# 2_FTDI.net
KiCad netlist of a schematic drawn in Altium Designer
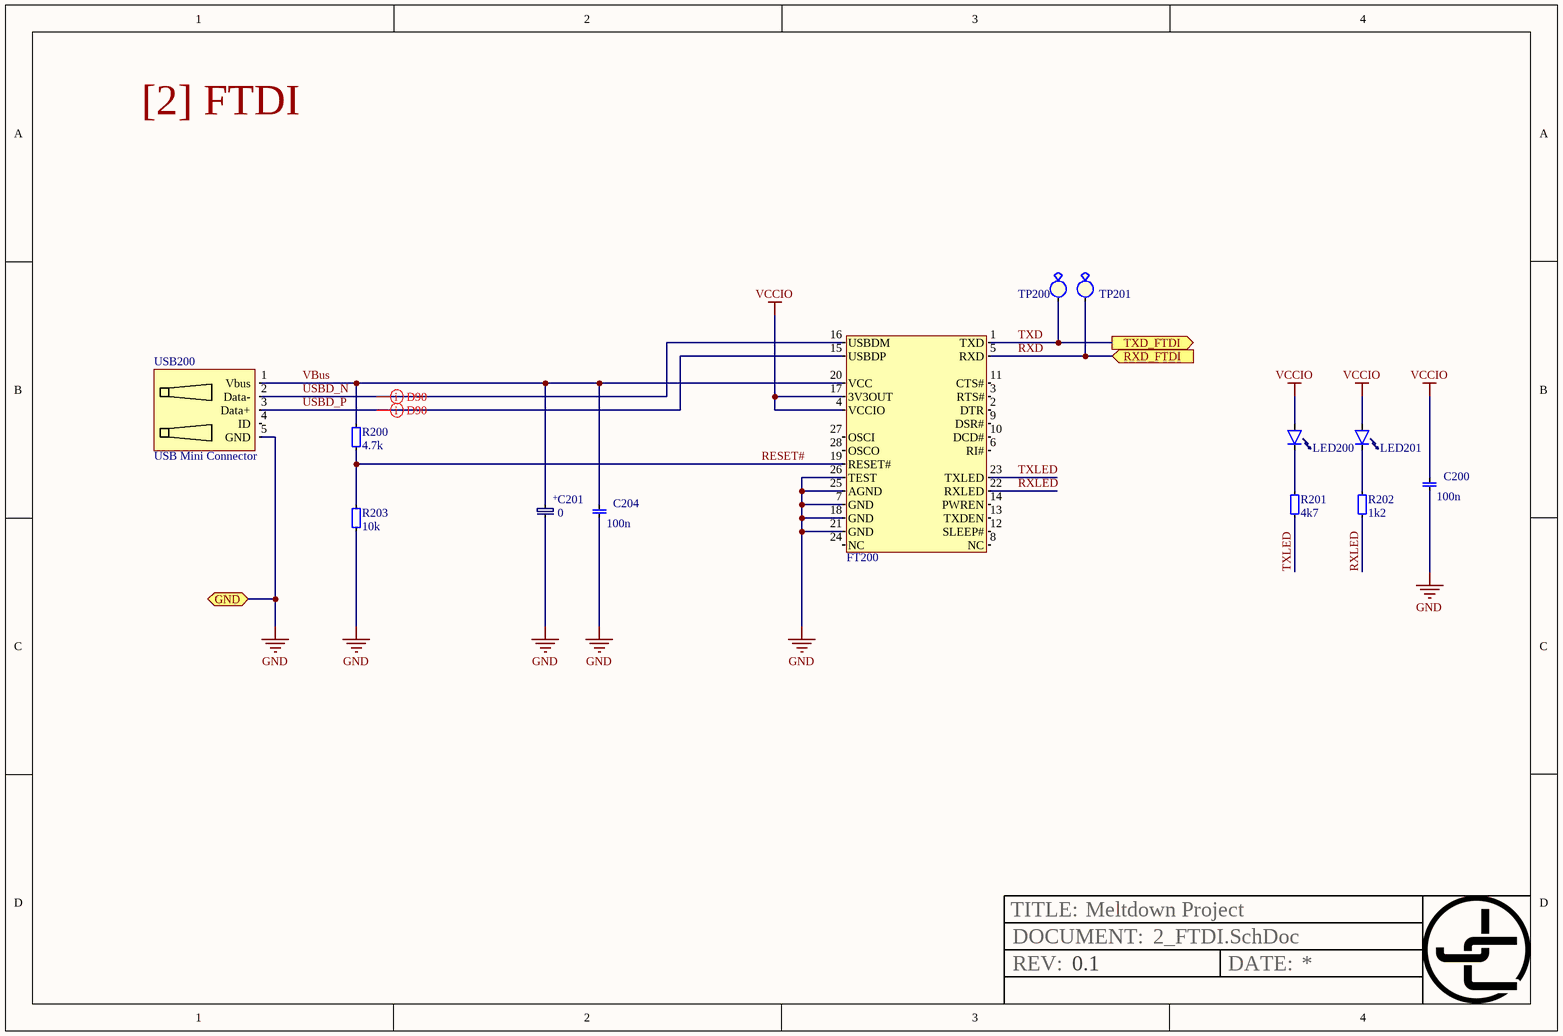
[diagram p0: 2_FTDI.SchDoc]

(export (version "E")
  (design (tool "Eeschema 10.0.6"))
  (components
    (comp (ref "C200")
      (value "100n")
      (footprint "0603 cap")
      (fields (field (name "Comment") "0603, capacitor"))
      (libsource (lib "jclib") (part "0603, capacitor"))
    )
    (comp (ref "C201")
      (value "0")
      (footprint "CASE_B")
      (fields (field (name "Comment") "Cap, case B"))
      (libsource (lib "jclib") (part "Cap, case B"))
    )
    (comp (ref "C204")
      (value "100n")
      (footprint "0603 cap")
      (fields (field (name "Comment") "0603, capacitor"))
      (libsource (lib "jclib") (part "0603, capacitor"))
    )
    (comp (ref "FT200")
      (value "FT232R")
      (footprint "SOP28")
      (description "USB UART IC")
      (libsource (lib "jclib") (part "FT232R"))
    )
    (comp (ref "LED200")
      (value "0805, LED")
      (footprint "0805_led")
      (libsource (lib "jclib") (part "0805, LED"))
    )
    (comp (ref "LED201")
      (value "0805, LED")
      (footprint "0805_led")
      (libsource (lib "jclib") (part "0805, LED"))
    )
    (comp (ref "R200")
      (value "4.7k")
      (footprint "0603")
      (fields (field (name "Comment") "0603, resistor"))
      (libsource (lib "jclib") (part "0603, resistor"))
    )
    (comp (ref "R201")
      (value "4k7")
      (footprint "0603")
      (fields (field (name "Comment") "0603, resistor"))
      (libsource (lib "jclib") (part "0603, resistor"))
    )
    (comp (ref "R202")
      (value "1k2")
      (footprint "0603")
      (fields (field (name "Comment") "0603, resistor"))
      (libsource (lib "jclib") (part "0603, resistor"))
    )
    (comp (ref "R203")
      (value "10k")
      (footprint "0603")
      (fields (field (name "Comment") "0603, resistor"))
      (libsource (lib "jclib") (part "0603, resistor"))
    )
    (comp (ref "TP200")
      (value "Test Point")
      (footprint "testPoint")
      (libsource (lib "jclib") (part "Test Point"))
    )
    (comp (ref "TP201")
      (value "Test Point")
      (footprint "testPoint")
      (libsource (lib "jclib") (part "Test Point"))
    )
    (comp (ref "USB200")
      (value "USB Mini Connector")
      (footprint "USB Mini TH")
      (libsource (lib "jclib") (part "USB Mini Connector"))
    )
  )
  (nets
    (net (code "1") (name "/RESET#") (class "Default")
      (node (ref "FT200") (pin "19") (pinfunction "RESET#_19") (pintype "passive"))
      (node (ref "R200") (pin "1") (pinfunction "1_1") (pintype "passive"))
      (node (ref "R203") (pin "0") (pinfunction "0_0") (pintype "passive"))
    )
    (net (code "2") (name "/RXD") (class "Default")
      (node (ref "FT200") (pin "5") (pinfunction "RXD_5") (pintype "passive"))
      (node (ref "TP201") (pin "0") (pinfunction "0_0") (pintype "passive"))
    )
    (net (code "3") (name "/RXLED") (class "Default")
      (node (ref "FT200") (pin "22") (pinfunction "RXLED_22") (pintype "passive"))
      (node (ref "R202") (pin "1") (pinfunction "1_1") (pintype "passive"))
    )
    (net (code "4") (name "/TXD") (class "Default")
      (node (ref "FT200") (pin "1") (pinfunction "TXD_1") (pintype "passive"))
      (node (ref "TP200") (pin "0") (pinfunction "0_0") (pintype "passive"))
    )
    (net (code "5") (name "/TXLED") (class "Default")
      (node (ref "FT200") (pin "23") (pinfunction "TXLED_23") (pintype "passive"))
      (node (ref "R201") (pin "1") (pinfunction "1_1") (pintype "passive"))
    )
    (net (code "6") (name "/USBD_N") (class "Default")
      (node (ref "FT200") (pin "16") (pinfunction "USBDM_16") (pintype "passive"))
      (node (ref "USB200") (pin "2") (pinfunction "Data-_2") (pintype "passive"))
    )
    (net (code "7") (name "/USBD_P") (class "Default")
      (node (ref "FT200") (pin "15") (pinfunction "USBDP_15") (pintype "passive"))
      (node (ref "USB200") (pin "3") (pinfunction "Data+_3") (pintype "passive"))
    )
    (net (code "8") (name "/VBus") (class "Default")
      (node (ref "C201") (pin "2") (pinfunction "2_2") (pintype "passive"))
      (node (ref "C204") (pin "1") (pinfunction "1_1") (pintype "passive"))
      (node (ref "FT200") (pin "20") (pinfunction "VCC_20") (pintype "passive"))
      (node (ref "R200") (pin "0") (pinfunction "0_0") (pintype "passive"))
      (node (ref "USB200") (pin "1") (pinfunction "Vbus_1") (pintype "passive"))
    )
    (net (code "9") (name "GND") (class "Default")
      (node (ref "C200") (pin "0") (pinfunction "0_0") (pintype "passive"))
      (node (ref "C201") (pin "1") (pinfunction "1_1") (pintype "passive"))
      (node (ref "C204") (pin "0") (pinfunction "0_0") (pintype "passive"))
      (node (ref "FT200") (pin "18") (pinfunction "GND_18") (pintype "passive"))
      (node (ref "FT200") (pin "21") (pinfunction "GND_21") (pintype "passive"))
      (node (ref "FT200") (pin "25") (pinfunction "AGND_25") (pintype "passive"))
      (node (ref "FT200") (pin "26") (pinfunction "TEST_26") (pintype "passive"))
      (node (ref "FT200") (pin "7") (pinfunction "GND_7") (pintype "passive"))
      (node (ref "R203") (pin "1") (pinfunction "1_1") (pintype "passive"))
      (node (ref "USB200") (pin "5") (pinfunction "GND_5") (pintype "passive"))
    )
    (net (code "10") (name "Net-(LED200-Cathode)") (class "Default")
      (node (ref "LED200") (pin "0") (pinfunction "Cathode_0") (pintype "passive"))
      (node (ref "R201") (pin "0") (pinfunction "0_0") (pintype "passive"))
    )
    (net (code "11") (name "Net-(LED201-Cathode)") (class "Default")
      (node (ref "LED201") (pin "0") (pinfunction "Cathode_0") (pintype "passive"))
      (node (ref "R202") (pin "0") (pinfunction "0_0") (pintype "passive"))
    )
    (net (code "12") (name "VCCIO") (class "Default")
      (node (ref "C200") (pin "1") (pinfunction "1_1") (pintype "passive"))
      (node (ref "FT200") (pin "17") (pinfunction "3V3OUT_17") (pintype "passive"))
      (node (ref "FT200") (pin "4") (pinfunction "VCCIO_4") (pintype "passive"))
      (node (ref "LED200") (pin "1") (pinfunction "1_1") (pintype "passive"))
      (node (ref "LED201") (pin "1") (pinfunction "1_1") (pintype "passive"))
    )
    (net (code "13") (name "unconnected-(FT200-CTS#-Pad11)") (class "Default")
      (node (ref "FT200") (pin "11") (pinfunction "CTS#_11") (pintype "passive"))
    )
    (net (code "14") (name "unconnected-(FT200-DCD#-Pad10)") (class "Default")
      (node (ref "FT200") (pin "10") (pinfunction "DCD#_10") (pintype "passive"))
    )
    (net (code "15") (name "unconnected-(FT200-DSR#-Pad9)") (class "Default")
      (node (ref "FT200") (pin "9") (pinfunction "DSR#_9") (pintype "passive"))
    )
    (net (code "16") (name "unconnected-(FT200-DTR-Pad2)") (class "Default")
      (node (ref "FT200") (pin "2") (pinfunction "DTR_2") (pintype "passive"))
    )
    (net (code "17") (name "unconnected-(FT200-NC-Pad8)") (class "Default")
      (node (ref "FT200") (pin "8") (pinfunction "NC_8") (pintype "passive"))
    )
    (net (code "18") (name "unconnected-(FT200-NC-Pad24)") (class "Default")
      (node (ref "FT200") (pin "24") (pinfunction "NC_24") (pintype "passive"))
    )
    (net (code "19") (name "unconnected-(FT200-OSCI-Pad27)") (class "Default")
      (node (ref "FT200") (pin "27") (pinfunction "OSCI_27") (pintype "passive"))
    )
    (net (code "20") (name "unconnected-(FT200-OSCO-Pad28)") (class "Default")
      (node (ref "FT200") (pin "28") (pinfunction "OSCO_28") (pintype "passive"))
    )
    (net (code "21") (name "unconnected-(FT200-PWREN-Pad14)") (class "Default")
      (node (ref "FT200") (pin "14") (pinfunction "PWREN_14") (pintype "passive"))
    )
    (net (code "22") (name "unconnected-(FT200-RI#-Pad6)") (class "Default")
      (node (ref "FT200") (pin "6") (pinfunction "RI#_6") (pintype "passive"))
    )
    (net (code "23") (name "unconnected-(FT200-RTS#-Pad3)") (class "Default")
      (node (ref "FT200") (pin "3") (pinfunction "RTS#_3") (pintype "passive"))
    )
    (net (code "24") (name "unconnected-(FT200-SLEEP#-Pad12)") (class "Default")
      (node (ref "FT200") (pin "12") (pinfunction "SLEEP#_12") (pintype "passive"))
    )
    (net (code "25") (name "unconnected-(FT200-TXDEN-Pad13)") (class "Default")
      (node (ref "FT200") (pin "13") (pinfunction "TXDEN_13") (pintype "passive"))
    )
    (net (code "26") (name "unconnected-(USB200-ID-Pad4)") (class "Default")
      (node (ref "USB200") (pin "4") (pinfunction "ID_4") (pintype "passive"))
    )
  )
)
